# design.net
KiCad netlist of a schematic drawn in Altium Designer
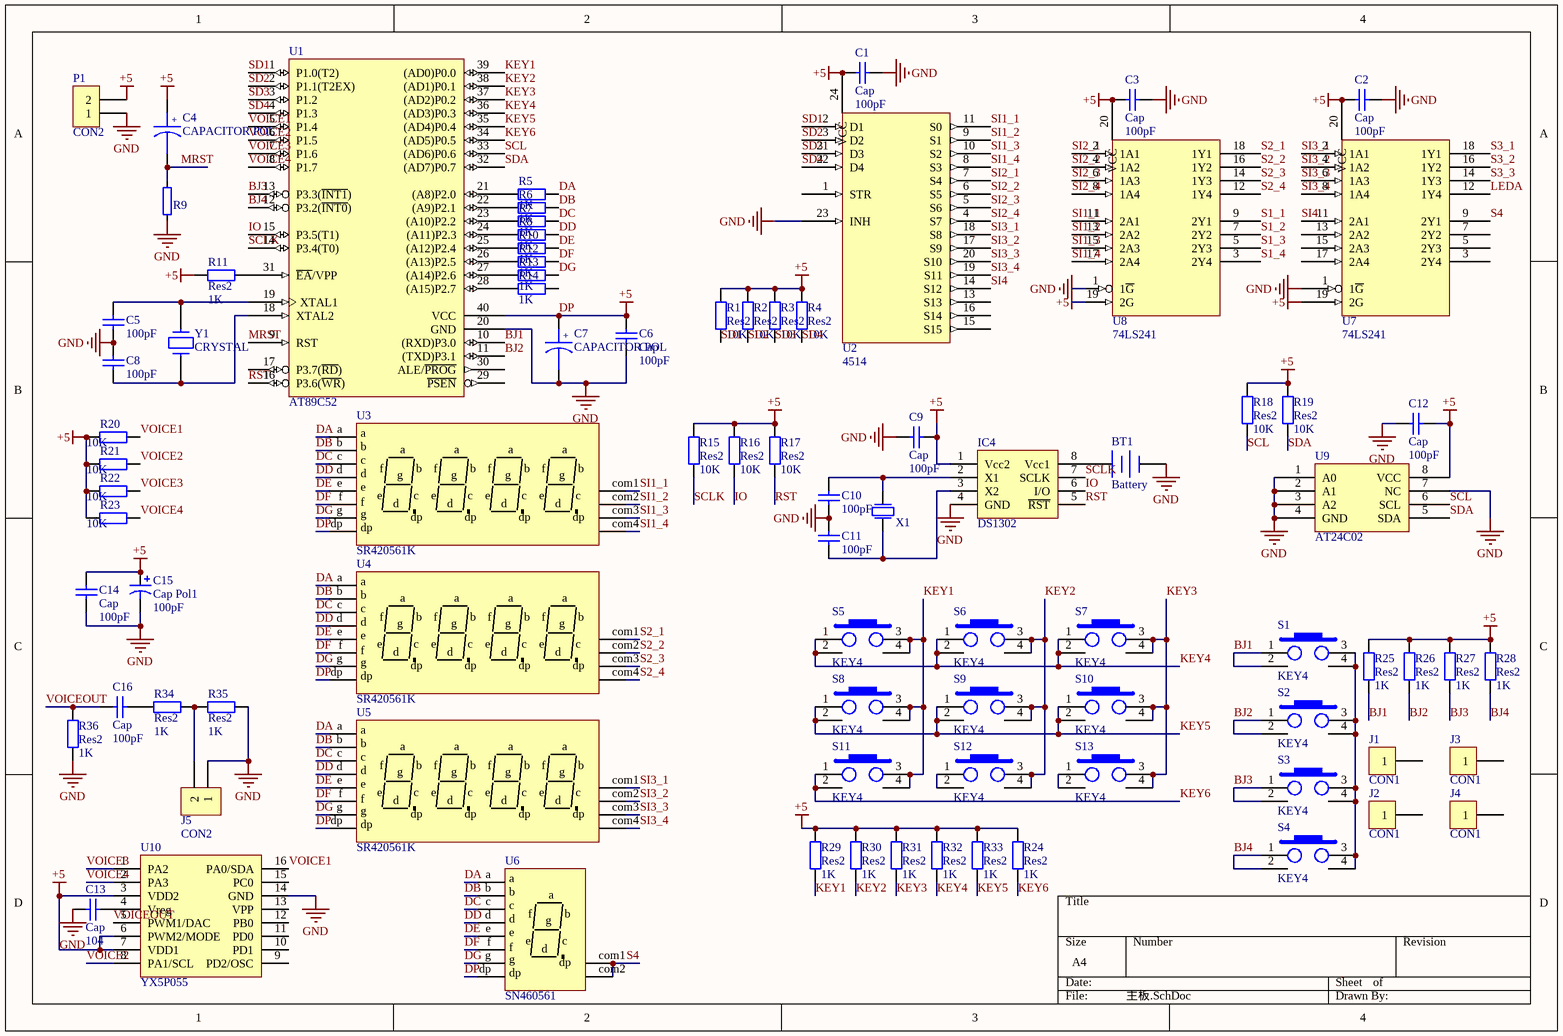
[diagram p0: 主板.SchDoc]

(export (version "E")
  (design (tool "Eeschema 10.0.6"))
  (components
    (comp (ref "BT1")
      (value "Battery")
      (footprint "CR2032-2")
      (description "Multicell Battery")
      (fields (field (name "PUBLISHER") "*"))
      (libsource (lib "mian") (part "Battery"))
    )
    (comp (ref "C1")
      (value "Cap")
      (footprint "RAD-0.3")
      (description "Capacitor")
      (fields (field (name "ALTIUM_VALUE") "100pF") (field (name "PUBLISHER") "Altium Limited"))
      (libsource (lib "Miscellaneous Devices") (part "Cap"))
    )
    (comp (ref "C2")
      (value "Cap")
      (footprint "RAD-0.3")
      (description "Capacitor")
      (fields (field (name "ALTIUM_VALUE") "100pF") (field (name "PUBLISHER") "Altium Limited"))
      (libsource (lib "Miscellaneous Devices") (part "Cap"))
    )
    (comp (ref "C3")
      (value "Cap")
      (footprint "RAD-0.3")
      (description "Capacitor")
      (fields (field (name "ALTIUM_VALUE") "100pF") (field (name "PUBLISHER") "Altium Limited"))
      (libsource (lib "Miscellaneous Devices") (part "Cap"))
    )
    (comp (ref "C4")
      (value "CAPACITOR POL")
      (footprint "22U1")
      (description "Capacitor")
      (libsource (lib "mian") (part "CAPACITOR POL"))
    )
    (comp (ref "C5")
      (value "100pF")
      (footprint "RAD-0.3")
      (description "Capacitor")
      (fields (field (name "Comment") "Cap") (field (name "PUBLISHER") "Altium Limited"))
      (libsource (lib "Miscellaneous Devices") (part "Cap"))
    )
    (comp (ref "C6")
      (value "Cap")
      (footprint "RAD-0.3")
      (description "Capacitor")
      (fields (field (name "ALTIUM_VALUE") "100pF") (field (name "PUBLISHER") "Altium Limited"))
      (libsource (lib "Miscellaneous Devices") (part "Cap"))
    )
    (comp (ref "C7")
      (value "CAPACITOR POL")
      (footprint "22U1")
      (description "Capacitor")
      (libsource (lib "mian") (part "CAPACITOR POL"))
    )
    (comp (ref "C8")
      (value "100pF")
      (footprint "RAD-0.3")
      (description "Capacitor")
      (fields (field (name "Comment") "Cap") (field (name "PUBLISHER") "Altium Limited"))
      (libsource (lib "Miscellaneous Devices") (part "Cap"))
    )
    (comp (ref "C9")
      (value "Cap")
      (footprint "RAD-0.3")
      (description "Capacitor")
      (fields (field (name "ALTIUM_VALUE") "100pF") (field (name "PUBLISHER") "Altium Limited"))
      (libsource (lib "Miscellaneous Devices") (part "Cap"))
    )
    (comp (ref "C10")
      (value "100pF")
      (footprint "RAD-0.3")
      (description "Capacitor")
      (fields (field (name "Comment") "Cap") (field (name "PUBLISHER") "Altium Limited"))
      (libsource (lib "Miscellaneous Devices") (part "Cap"))
    )
    (comp (ref "C11")
      (value "100pF")
      (footprint "RAD-0.3")
      (description "Capacitor")
      (fields (field (name "Comment") "Cap") (field (name "PUBLISHER") "Altium Limited"))
      (libsource (lib "Miscellaneous Devices") (part "Cap"))
    )
    (comp (ref "C12")
      (value "Cap")
      (footprint "RAD-0.3")
      (description "Capacitor")
      (fields (field (name "ALTIUM_VALUE") "100pF") (field (name "PUBLISHER") "Altium Limited"))
      (libsource (lib "Miscellaneous Devices") (part "Cap"))
    )
    (comp (ref "C13")
      (value "Cap")
      (footprint "RAD-0.3")
      (description "Capacitor")
      (fields (field (name "ALTIUM_VALUE") "104") (field (name "PUBLISHER") "Altium Limited"))
      (libsource (lib "Miscellaneous Devices") (part "Cap"))
    )
    (comp (ref "C14")
      (value "Cap")
      (footprint "RAD-0.3")
      (description "Capacitor")
      (fields (field (name "ALTIUM_VALUE") "100pF") (field (name "PUBLISHER") "Altium Limited"))
      (libsource (lib "Miscellaneous Devices") (part "Cap"))
    )
    (comp (ref "C15")
      (value "Cap Pol1")
      (footprint "RB7.6-15")
      (description "Polarized Capacitor (Radial)")
      (fields (field (name "ALTIUM_VALUE") "100pF") (field (name "PUBLISHER") "Altium Limited"))
      (libsource (lib "Miscellaneous Devices") (part "Cap Pol1"))
    )
    (comp (ref "C16")
      (value "Cap")
      (footprint "RAD-0.3")
      (description "Capacitor")
      (fields (field (name "ALTIUM_VALUE") "100pF") (field (name "PUBLISHER") "Altium Limited"))
      (libsource (lib "Miscellaneous Devices") (part "Cap"))
    )
    (comp (ref "IC4") (value "DS1302") (footprint "DIP8") (libsource (lib "mian") (part "DS1302")))
    (comp (ref "J1")
      (value "CON1")
      (footprint "GDK")
      (description "Connector")
      (libsource (lib "mian") (part "CON1"))
    )
    (comp (ref "J2")
      (value "CON1")
      (footprint "GDK")
      (description "Connector")
      (libsource (lib "mian") (part "CON1"))
    )
    (comp (ref "J3")
      (value "CON1")
      (footprint "GDK")
      (description "Connector")
      (libsource (lib "mian") (part "CON1"))
    )
    (comp (ref "J4")
      (value "CON1")
      (footprint "GDK")
      (description "Connector")
      (libsource (lib "mian") (part "CON1"))
    )
    (comp (ref "J5")
      (value "CON2")
      (footprint "VOICE-1")
      (description "Connector")
      (libsource (lib "gf-sch") (part "CON2"))
    )
    (comp (ref "P1")
      (value "CON2")
      (footprint "VOICE-1")
      (description "Connector")
      (libsource (lib "") (part "CON2_1"))
    )
    (comp (ref "R1")
      (value "Res2")
      (footprint "AXIAL-0.4")
      (description "Resistor")
      (fields (field (name "ALTIUM_VALUE") "10K") (field (name "PUBLISHER") "Altium Limited"))
      (libsource (lib "") (part "Res2_2"))
    )
    (comp (ref "R2")
      (value "Res2")
      (footprint "AXIAL-0.4")
      (description "Resistor")
      (fields (field (name "ALTIUM_VALUE") "10K") (field (name "PUBLISHER") "Altium Limited"))
      (libsource (lib "") (part "Res2_2"))
    )
    (comp (ref "R3")
      (value "Res2")
      (footprint "AXIAL-0.4")
      (description "Resistor")
      (fields (field (name "ALTIUM_VALUE") "10K") (field (name "PUBLISHER") "Altium Limited"))
      (libsource (lib "") (part "Res2_2"))
    )
    (comp (ref "R4")
      (value "Res2")
      (footprint "AXIAL-0.4")
      (description "Resistor")
      (fields (field (name "ALTIUM_VALUE") "10K") (field (name "PUBLISHER") "Altium Limited"))
      (libsource (lib "") (part "Res2_2"))
    )
    (comp (ref "R5")
      (value "1K")
      (footprint "AXIAL-0.4")
      (description "Resistor")
      (fields (field (name "Comment") "Res2") (field (name "PUBLISHER") "Altium Limited"))
      (libsource (lib "") (part "Res2_1"))
    )
    (comp (ref "R6")
      (value "1K")
      (footprint "AXIAL-0.4")
      (description "Resistor")
      (fields (field (name "Comment") "Res2") (field (name "PUBLISHER") "Altium Limited"))
      (libsource (lib "") (part "Res2_1"))
    )
    (comp (ref "R7")
      (value "1K")
      (footprint "AXIAL-0.4")
      (description "Resistor")
      (fields (field (name "Comment") "Res2") (field (name "PUBLISHER") "Altium Limited"))
      (libsource (lib "") (part "Res2_1"))
    )
    (comp (ref "R8")
      (value "1K")
      (footprint "AXIAL-0.4")
      (description "Resistor")
      (fields (field (name "Comment") "Res2") (field (name "PUBLISHER") "Altium Limited"))
      (libsource (lib "") (part "Res2_1"))
    )
    (comp (ref "R9")
      (value "R-10K")
      (footprint "0805R")
      (description "resistor")
      (libsource (lib "mian") (part "R-10K"))
    )
    (comp (ref "R10")
      (value "1K")
      (footprint "AXIAL-0.4")
      (description "Resistor")
      (fields (field (name "Comment") "Res2") (field (name "PUBLISHER") "Altium Limited"))
      (libsource (lib "") (part "Res2_1"))
    )
    (comp (ref "R11")
      (value "Res2")
      (footprint "AXIAL-0.4")
      (description "Resistor")
      (fields (field (name "ALTIUM_VALUE") "1K") (field (name "PUBLISHER") "Altium Limited"))
      (libsource (lib "") (part "Res2_1"))
    )
    (comp (ref "R12")
      (value "1K")
      (footprint "AXIAL-0.4")
      (description "Resistor")
      (fields (field (name "Comment") "Res2") (field (name "PUBLISHER") "Altium Limited"))
      (libsource (lib "") (part "Res2_1"))
    )
    (comp (ref "R13")
      (value "1K")
      (footprint "AXIAL-0.4")
      (description "Resistor")
      (fields (field (name "Comment") "Res2") (field (name "PUBLISHER") "Altium Limited"))
      (libsource (lib "") (part "Res2_1"))
    )
    (comp (ref "R14")
      (value "1K")
      (footprint "AXIAL-0.4")
      (description "Resistor")
      (fields (field (name "Comment") "Res2") (field (name "PUBLISHER") "Altium Limited"))
      (libsource (lib "") (part "Res2_1"))
    )
    (comp (ref "R15")
      (value "Res2")
      (footprint "AXIAL-0.4")
      (description "Resistor")
      (fields (field (name "ALTIUM_VALUE") "10K") (field (name "PUBLISHER") "Altium Limited"))
      (libsource (lib "") (part "Res2_2"))
    )
    (comp (ref "R16")
      (value "Res2")
      (footprint "AXIAL-0.4")
      (description "Resistor")
      (fields (field (name "ALTIUM_VALUE") "10K") (field (name "PUBLISHER") "Altium Limited"))
      (libsource (lib "") (part "Res2_2"))
    )
    (comp (ref "R17")
      (value "Res2")
      (footprint "AXIAL-0.4")
      (description "Resistor")
      (fields (field (name "ALTIUM_VALUE") "10K") (field (name "PUBLISHER") "Altium Limited"))
      (libsource (lib "") (part "Res2_2"))
    )
    (comp (ref "R18")
      (value "Res2")
      (footprint "AXIAL-0.4")
      (description "Resistor")
      (fields (field (name "ALTIUM_VALUE") "10K") (field (name "PUBLISHER") "Altium Limited"))
      (libsource (lib "") (part "Res2_2"))
    )
    (comp (ref "R19")
      (value "Res2")
      (footprint "AXIAL-0.4")
      (description "Resistor")
      (fields (field (name "ALTIUM_VALUE") "10K") (field (name "PUBLISHER") "Altium Limited"))
      (libsource (lib "") (part "Res2_2"))
    )
    (comp (ref "R20")
      (value "10K")
      (footprint "AXIAL-0.4")
      (description "Resistor")
      (fields (field (name "Comment") "Res2") (field (name "PUBLISHER") "Altium Limited"))
      (libsource (lib "Miscellaneous Devices") (part "Res2"))
    )
    (comp (ref "R21")
      (value "10K")
      (footprint "AXIAL-0.4")
      (description "Resistor")
      (fields (field (name "Comment") "Res2") (field (name "PUBLISHER") "Altium Limited"))
      (libsource (lib "Miscellaneous Devices") (part "Res2"))
    )
    (comp (ref "R22")
      (value "10K")
      (footprint "AXIAL-0.4")
      (description "Resistor")
      (fields (field (name "Comment") "Res2") (field (name "PUBLISHER") "Altium Limited"))
      (libsource (lib "Miscellaneous Devices") (part "Res2"))
    )
    (comp (ref "R23")
      (value "10K")
      (footprint "AXIAL-0.4")
      (description "Resistor")
      (fields (field (name "Comment") "Res2") (field (name "PUBLISHER") "Altium Limited"))
      (libsource (lib "Miscellaneous Devices") (part "Res2"))
    )
    (comp (ref "R24")
      (value "Res2")
      (footprint "AXIAL-0.4")
      (description "Resistor")
      (fields (field (name "ALTIUM_VALUE") "1K") (field (name "PUBLISHER") "Altium Limited"))
      (libsource (lib "") (part "Res2_2"))
    )
    (comp (ref "R25")
      (value "Res2")
      (footprint "AXIAL-0.4")
      (description "Resistor")
      (fields (field (name "ALTIUM_VALUE") "1K") (field (name "PUBLISHER") "Altium Limited"))
      (libsource (lib "") (part "Res2_2"))
    )
    (comp (ref "R26")
      (value "Res2")
      (footprint "AXIAL-0.4")
      (description "Resistor")
      (fields (field (name "ALTIUM_VALUE") "1K") (field (name "PUBLISHER") "Altium Limited"))
      (libsource (lib "") (part "Res2_2"))
    )
    (comp (ref "R27")
      (value "Res2")
      (footprint "AXIAL-0.4")
      (description "Resistor")
      (fields (field (name "ALTIUM_VALUE") "1K") (field (name "PUBLISHER") "Altium Limited"))
      (libsource (lib "") (part "Res2_2"))
    )
    (comp (ref "R28")
      (value "Res2")
      (footprint "AXIAL-0.4")
      (description "Resistor")
      (fields (field (name "ALTIUM_VALUE") "1K") (field (name "PUBLISHER") "Altium Limited"))
      (libsource (lib "") (part "Res2_2"))
    )
    (comp (ref "R29")
      (value "Res2")
      (footprint "AXIAL-0.4")
      (description "Resistor")
      (fields (field (name "ALTIUM_VALUE") "1K") (field (name "PUBLISHER") "Altium Limited"))
      (libsource (lib "") (part "Res2_2"))
    )
    (comp (ref "R30")
      (value "Res2")
      (footprint "AXIAL-0.4")
      (description "Resistor")
      (fields (field (name "ALTIUM_VALUE") "1K") (field (name "PUBLISHER") "Altium Limited"))
      (libsource (lib "") (part "Res2_2"))
    )
    (comp (ref "R31")
      (value "Res2")
      (footprint "AXIAL-0.4")
      (description "Resistor")
      (fields (field (name "ALTIUM_VALUE") "1K") (field (name "PUBLISHER") "Altium Limited"))
      (libsource (lib "") (part "Res2_2"))
    )
    (comp (ref "R32")
      (value "Res2")
      (footprint "AXIAL-0.4")
      (description "Resistor")
      (fields (field (name "ALTIUM_VALUE") "1K") (field (name "PUBLISHER") "Altium Limited"))
      (libsource (lib "") (part "Res2_2"))
    )
    (comp (ref "R33")
      (value "Res2")
      (footprint "AXIAL-0.4")
      (description "Resistor")
      (fields (field (name "ALTIUM_VALUE") "1K") (field (name "PUBLISHER") "Altium Limited"))
      (libsource (lib "") (part "Res2_2"))
    )
    (comp (ref "R34")
      (value "Res2")
      (footprint "AXIAL-0.4")
      (description "Resistor")
      (fields (field (name "ALTIUM_VALUE") "1K") (field (name "PUBLISHER") "Altium Limited"))
      (libsource (lib "") (part "Res2_1"))
    )
    (comp (ref "R35")
      (value "Res2")
      (footprint "AXIAL-0.4")
      (description "Resistor")
      (fields (field (name "ALTIUM_VALUE") "1K") (field (name "PUBLISHER") "Altium Limited"))
      (libsource (lib "") (part "Res2_1"))
    )
    (comp (ref "R36")
      (value "Res2")
      (footprint "AXIAL-0.4")
      (description "Resistor")
      (fields (field (name "ALTIUM_VALUE") "1K") (field (name "PUBLISHER") "Altium Limited"))
      (libsource (lib "") (part "Res2_2"))
    )
    (comp (ref "S1") (value "KEY4") (footprint "PUSH12") (libsource (lib "mian") (part "KEY4")))
    (comp (ref "S2") (value "KEY4") (footprint "PUSH12") (libsource (lib "mian") (part "KEY4")))
    (comp (ref "S3") (value "KEY4") (footprint "PUSH12") (libsource (lib "mian") (part "KEY4")))
    (comp (ref "S4") (value "KEY4") (footprint "PUSH12") (libsource (lib "mian") (part "KEY4")))
    (comp (ref "S5") (value "KEY4") (footprint "PUSH12") (libsource (lib "mian") (part "KEY4")))
    (comp (ref "S6") (value "KEY4") (footprint "PUSH12") (libsource (lib "mian") (part "KEY4")))
    (comp (ref "S7") (value "KEY4") (footprint "PUSH12") (libsource (lib "mian") (part "KEY4")))
    (comp (ref "S8") (value "KEY4") (footprint "PUSH12") (libsource (lib "mian") (part "KEY4")))
    (comp (ref "S9") (value "KEY4") (footprint "PUSH12") (libsource (lib "mian") (part "KEY4")))
    (comp (ref "S10") (value "KEY4") (footprint "PUSH12") (libsource (lib "mian") (part "KEY4")))
    (comp (ref "S11") (value "KEY4") (footprint "PUSH12") (libsource (lib "mian") (part "KEY4")))
    (comp (ref "S12") (value "KEY4") (footprint "PUSH12") (libsource (lib "mian") (part "KEY4")))
    (comp (ref "S13") (value "KEY4") (footprint "PUSH12") (libsource (lib "mian") (part "KEY4")))
    (comp (ref "U1")
      (value "AT89C52")
      (footprint "DIP40")
      (description "8-Bit Microcontroller with 8K Flash ROM")
      (libsource (lib "mian") (part "AT89C52"))
    )
    (comp (ref "U2") (value "4514") (footprint "SOP4510") (libsource (lib "mian") (part "4514")))
    (comp (ref "U3")
      (value "SR420561K")
      (footprint "5462B")
      (description "CP-SR420561K")
      (libsource (lib "mian") (part "SR420561K"))
    )
    (comp (ref "U4")
      (value "SR420561K")
      (footprint "5462B")
      (description "CP-SR420561K")
      (libsource (lib "mian") (part "SR420561K"))
    )
    (comp (ref "U5")
      (value "SR420561K")
      (footprint "5462B")
      (description "CP-SR420561K")
      (libsource (lib "mian") (part "SR420561K"))
    )
    (comp (ref "U6")
      (value "SN460561")
      (footprint "3121B")
      (description "CP-SN460561K")
      (libsource (lib "mian") (part "SN460561"))
    )
    (comp (ref "U7") (value "74LS241") (footprint "SOP241") (libsource (lib "mian") (part "74LS241")))
    (comp (ref "U8") (value "74LS241") (footprint "SOP241") (libsource (lib "mian") (part "74LS241")))
    (comp (ref "U9")
      (value "AT24C02")
      (footprint "DIP8")
      (description "U?")
      (libsource (lib "mian") (part "AT24C02"))
    )
    (comp (ref "U10") (value "YX5P055") (footprint "DIP16") (libsource (lib "mian2") (part "YX5P055")))
    (comp (ref "X1") (value "XTAL1") (footprint "X2") (libsource (lib "mian") (part "XTAL1")))
    (comp (ref "Y1")
      (value "CRYSTAL")
      (footprint "OSC2PR-1")
      (description "Crystal")
      (libsource (lib "mian") (part "CRYSTAL"))
    )
  )
  (nets
    (net (code "1") (name "+5") (class "Default")
      (node (ref "C1") (pin "2") (pinfunction "2_2") (pintype "passive"))
      (node (ref "C12") (pin "2") (pinfunction "2_2") (pintype "passive"))
      (node (ref "C14") (pin "2") (pinfunction "2_2") (pintype "passive"))
      (node (ref "C15") (pin "1") (pinfunction "1_1") (pintype "passive"))
      (node (ref "C2") (pin "2") (pinfunction "2_2") (pintype "passive"))
      (node (ref "C3") (pin "2") (pinfunction "2_2") (pintype "passive"))
      (node (ref "C4") (pin "1") (pinfunction "1_1") (pintype "passive"))
      (node (ref "C6") (pin "1") (pinfunction "1_1") (pintype "passive"))
      (node (ref "C7") (pin "1") (pinfunction "1_1") (pintype "passive"))
      (node (ref "C9") (pin "2") (pinfunction "2_2") (pintype "passive"))
      (node (ref "IC4") (pin "1") (pinfunction "Vcc2_1") (pintype "passive"))
      (node (ref "P1") (pin "2") (pinfunction "2_2") (pintype "passive"))
      (node (ref "R1") (pin "2") (pinfunction "2_2") (pintype "passive"))
      (node (ref "R11") (pin "1") (pinfunction "1_1") (pintype "passive"))
      (node (ref "R15") (pin "2") (pinfunction "2_2") (pintype "passive"))
      (node (ref "R16") (pin "2") (pinfunction "2_2") (pintype "passive"))
      (node (ref "R17") (pin "2") (pinfunction "2_2") (pintype "passive"))
      (node (ref "R18") (pin "2") (pinfunction "2_2") (pintype "passive"))
      (node (ref "R19") (pin "2") (pinfunction "2_2") (pintype "passive"))
      (node (ref "R2") (pin "2") (pinfunction "2_2") (pintype "passive"))
      (node (ref "R20") (pin "2") (pinfunction "2_2") (pintype "passive"))
      (node (ref "R21") (pin "2") (pinfunction "2_2") (pintype "passive"))
      (node (ref "R22") (pin "2") (pinfunction "2_2") (pintype "passive"))
      (node (ref "R23") (pin "2") (pinfunction "2_2") (pintype "passive"))
      (node (ref "R24") (pin "2") (pinfunction "2_2") (pintype "passive"))
      (node (ref "R25") (pin "2") (pinfunction "2_2") (pintype "passive"))
      (node (ref "R26") (pin "2") (pinfunction "2_2") (pintype "passive"))
      (node (ref "R27") (pin "2") (pinfunction "2_2") (pintype "passive"))
      (node (ref "R28") (pin "2") (pinfunction "2_2") (pintype "passive"))
      (node (ref "R29") (pin "2") (pinfunction "2_2") (pintype "passive"))
      (node (ref "R3") (pin "2") (pinfunction "2_2") (pintype "passive"))
      (node (ref "R30") (pin "2") (pinfunction "2_2") (pintype "passive"))
      (node (ref "R31") (pin "2") (pinfunction "2_2") (pintype "passive"))
      (node (ref "R32") (pin "2") (pinfunction "2_2") (pintype "passive"))
      (node (ref "R33") (pin "2") (pinfunction "2_2") (pintype "passive"))
      (node (ref "R4") (pin "2") (pinfunction "2_2") (pintype "passive"))
      (node (ref "U1") (pin "40") (pinfunction "VCC_40") (pintype "power_in"))
      (node (ref "U10") (pin "3") (pinfunction "VDD2_3") (pintype "passive"))
      (node (ref "U10") (pin "6") (pinfunction "PWM2/MODE_6") (pintype "passive"))
      (node (ref "U10") (pin "7") (pinfunction "VDD1_7") (pintype "passive"))
      (node (ref "U2") (pin "24") (pinfunction "VCC_24") (pintype "power_in"))
      (node (ref "U3") (pin "dp") (pinfunction "dp_dp") (pintype "passive"))
      (node (ref "U4") (pin "dp") (pinfunction "dp_dp") (pintype "passive"))
      (node (ref "U5") (pin "dp") (pinfunction "dp_dp") (pintype "passive"))
      (node (ref "U6") (pin "dp") (pinfunction "dp_dp") (pintype "passive"))
      (node (ref "U7") (pin "19") (pinfunction "2G_19") (pintype "input"))
      (node (ref "U7") (pin "20") (pinfunction "VCC_20") (pintype "power_in"))
      (node (ref "U8") (pin "19") (pinfunction "2G_19") (pintype "input"))
      (node (ref "U8") (pin "20") (pinfunction "VCC_20") (pintype "power_in"))
      (node (ref "U9") (pin "8") (pinfunction "VCC_8") (pintype "passive"))
    )
    (net (code "2") (name "/BJ1") (class "Default")
      (node (ref "R25") (pin "1") (pinfunction "1_1") (pintype "passive"))
      (node (ref "S1") (pin "1") (pintype "passive"))
      (node (ref "S1") (pin "2") (pintype "passive"))
      (node (ref "U1") (pin "10") (pinfunction "(RXD)P3.0_10") (pintype "bidirectional"))
    )
    (net (code "3") (name "/BJ2") (class "Default")
      (node (ref "R26") (pin "1") (pinfunction "1_1") (pintype "passive"))
      (node (ref "S2") (pin "1") (pintype "passive"))
      (node (ref "S2") (pin "2") (pintype "passive"))
      (node (ref "U1") (pin "11") (pinfunction "(TXD)P3.1_11") (pintype "bidirectional"))
    )
    (net (code "4") (name "/BJ3") (class "Default")
      (node (ref "R27") (pin "1") (pinfunction "1_1") (pintype "passive"))
      (node (ref "S3") (pin "1") (pintype "passive"))
      (node (ref "S3") (pin "2") (pintype "passive"))
      (node (ref "U1") (pin "13") (pinfunction "P3.3(~{INT1})_13") (pintype "bidirectional"))
    )
    (net (code "5") (name "/BJ4") (class "Default")
      (node (ref "R28") (pin "1") (pinfunction "1_1") (pintype "passive"))
      (node (ref "S4") (pin "1") (pintype "passive"))
      (node (ref "S4") (pin "2") (pintype "passive"))
      (node (ref "U1") (pin "12") (pinfunction "P3.2(~{INT0})_12") (pintype "bidirectional"))
    )
    (net (code "6") (name "/DA") (class "Default")
      (node (ref "R5") (pin "2") (pinfunction "2_2") (pintype "passive"))
      (node (ref "U3") (pin "a") (pinfunction "a_a") (pintype "passive"))
      (node (ref "U4") (pin "a") (pinfunction "a_a") (pintype "passive"))
      (node (ref "U5") (pin "a") (pinfunction "a_a") (pintype "passive"))
      (node (ref "U6") (pin "a") (pinfunction "a_a") (pintype "passive"))
    )
    (net (code "7") (name "/DB") (class "Default")
      (node (ref "R6") (pin "2") (pinfunction "2_2") (pintype "passive"))
      (node (ref "U3") (pin "b") (pinfunction "b_b") (pintype "passive"))
      (node (ref "U4") (pin "b") (pinfunction "b_b") (pintype "passive"))
      (node (ref "U5") (pin "b") (pinfunction "b_b") (pintype "passive"))
      (node (ref "U6") (pin "b") (pinfunction "b_b") (pintype "passive"))
    )
    (net (code "8") (name "/DC") (class "Default")
      (node (ref "R7") (pin "2") (pinfunction "2_2") (pintype "passive"))
      (node (ref "U3") (pin "c") (pinfunction "c_c") (pintype "passive"))
      (node (ref "U4") (pin "c") (pinfunction "c_c") (pintype "passive"))
      (node (ref "U5") (pin "c") (pinfunction "c_c") (pintype "passive"))
      (node (ref "U6") (pin "c") (pinfunction "c_c") (pintype "passive"))
    )
    (net (code "9") (name "/DD") (class "Default")
      (node (ref "R8") (pin "2") (pinfunction "2_2") (pintype "passive"))
      (node (ref "U3") (pin "d") (pinfunction "d_d") (pintype "passive"))
      (node (ref "U4") (pin "d") (pinfunction "d_d") (pintype "passive"))
      (node (ref "U5") (pin "d") (pinfunction "d_d") (pintype "passive"))
      (node (ref "U6") (pin "d") (pinfunction "d_d") (pintype "passive"))
    )
    (net (code "10") (name "/DE") (class "Default")
      (node (ref "R10") (pin "2") (pinfunction "2_2") (pintype "passive"))
      (node (ref "U3") (pin "e") (pinfunction "e_e") (pintype "passive"))
      (node (ref "U4") (pin "e") (pinfunction "e_e") (pintype "passive"))
      (node (ref "U5") (pin "e") (pinfunction "e_e") (pintype "passive"))
      (node (ref "U6") (pin "e") (pinfunction "e_e") (pintype "passive"))
    )
    (net (code "11") (name "/DF") (class "Default")
      (node (ref "R12") (pin "2") (pinfunction "2_2") (pintype "passive"))
      (node (ref "U3") (pin "f") (pinfunction "f_f") (pintype "passive"))
      (node (ref "U4") (pin "f") (pinfunction "f_f") (pintype "passive"))
      (node (ref "U5") (pin "f") (pinfunction "f_f") (pintype "passive"))
      (node (ref "U6") (pin "f") (pinfunction "f_f") (pintype "passive"))
    )
    (net (code "12") (name "/DG") (class "Default")
      (node (ref "R13") (pin "2") (pinfunction "2_2") (pintype "passive"))
      (node (ref "U3") (pin "g") (pinfunction "g_g") (pintype "passive"))
      (node (ref "U4") (pin "g") (pinfunction "g_g") (pintype "passive"))
      (node (ref "U5") (pin "g") (pinfunction "g_g") (pintype "passive"))
      (node (ref "U6") (pin "g") (pinfunction "g_g") (pintype "passive"))
    )
    (net (code "13") (name "/IO") (class "Default")
      (node (ref "IC4") (pin "6") (pinfunction "I/O_6") (pintype "passive"))
      (node (ref "R16") (pin "1") (pinfunction "1_1") (pintype "passive"))
      (node (ref "U1") (pin "15") (pinfunction "P3.5(T1)_15") (pintype "bidirectional"))
    )
    (net (code "14") (name "/KEY1") (class "Default")
      (node (ref "R29") (pin "1") (pinfunction "1_1") (pintype "passive"))
      (node (ref "S11") (pin "3") (pintype "passive"))
      (node (ref "S11") (pin "4") (pintype "passive"))
      (node (ref "S5") (pin "3") (pintype "passive"))
      (node (ref "S5") (pin "4") (pintype "passive"))
      (node (ref "S8") (pin "3") (pintype "passive"))
      (node (ref "S8") (pin "4") (pintype "passive"))
      (node (ref "U1") (pin "39") (pinfunction "(AD0)P0.0_39") (pintype "bidirectional"))
    )
    (net (code "15") (name "/KEY2") (class "Default")
      (node (ref "R30") (pin "1") (pinfunction "1_1") (pintype "passive"))
      (node (ref "S12") (pin "3") (pintype "passive"))
      (node (ref "S12") (pin "4") (pintype "passive"))
      (node (ref "S6") (pin "3") (pintype "passive"))
      (node (ref "S6") (pin "4") (pintype "passive"))
      (node (ref "S9") (pin "3") (pintype "passive"))
      (node (ref "S9") (pin "4") (pintype "passive"))
      (node (ref "U1") (pin "38") (pinfunction "(AD1)P0.1_38") (pintype "bidirectional"))
    )
    (net (code "16") (name "/KEY3") (class "Default")
      (node (ref "R31") (pin "1") (pinfunction "1_1") (pintype "passive"))
      (node (ref "S10") (pin "3") (pintype "passive"))
      (node (ref "S10") (pin "4") (pintype "passive"))
      (node (ref "S13") (pin "3") (pintype "passive"))
      (node (ref "S13") (pin "4") (pintype "passive"))
      (node (ref "S7") (pin "3") (pintype "passive"))
      (node (ref "S7") (pin "4") (pintype "passive"))
      (node (ref "U1") (pin "37") (pinfunction "(AD2)P0.2_37") (pintype "bidirectional"))
    )
    (net (code "17") (name "/KEY4") (class "Default")
      (node (ref "R32") (pin "1") (pinfunction "1_1") (pintype "passive"))
      (node (ref "S5") (pin "1") (pintype "passive"))
      (node (ref "S5") (pin "2") (pintype "passive"))
      (node (ref "S6") (pin "1") (pintype "passive"))
      (node (ref "S6") (pin "2") (pintype "passive"))
      (node (ref "S7") (pin "1") (pintype "passive"))
      (node (ref "S7") (pin "2") (pintype "passive"))
      (node (ref "U1") (pin "36") (pinfunction "(AD3)P0.3_36") (pintype "bidirectional"))
    )
    (net (code "18") (name "/KEY5") (class "Default")
      (node (ref "R33") (pin "1") (pinfunction "1_1") (pintype "passive"))
      (node (ref "S10") (pin "1") (pintype "passive"))
      (node (ref "S10") (pin "2") (pintype "passive"))
      (node (ref "S8") (pin "1") (pintype "passive"))
      (node (ref "S8") (pin "2") (pintype "passive"))
      (node (ref "S9") (pin "1") (pintype "passive"))
      (node (ref "S9") (pin "2") (pintype "passive"))
      (node (ref "U1") (pin "35") (pinfunction "(AD4)P0.4_35") (pintype "bidirectional"))
    )
    (net (code "19") (name "/KEY6") (class "Default")
      (node (ref "R24") (pin "1") (pinfunction "1_1") (pintype "passive"))
      (node (ref "S11") (pin "1") (pintype "passive"))
      (node (ref "S11") (pin "2") (pintype "passive"))
      (node (ref "U1") (pin "34") (pinfunction "(AD5)P0.5_34") (pintype "bidirectional"))
    )
    (net (code "20") (name "/LEDA") (class "Default")
      (node (ref "U7") (pin "12") (pinfunction "1Y4_12") (pintype "tri_state"))
    )
    (net (code "21") (name "/MRST") (class "Default")
      (node (ref "C4") (pin "2") (pinfunction "2_2") (pintype "passive"))
      (node (ref "R9") (pin "2") (pinfunction "2_2") (pintype "passive"))
      (node (ref "U1") (pin "9") (pinfunction "RST_9") (pintype "input"))
    )
    (net (code "22") (name "/RST") (class "Default")
      (node (ref "IC4") (pin "5") (pinfunction "~{RST}_5") (pintype "passive"))
      (node (ref "R17") (pin "1") (pinfunction "1_1") (pintype "passive"))
      (node (ref "U1") (pin "16") (pinfunction "P3.6(~{WR})_16") (pintype "bidirectional"))
    )
    (net (code "23") (name "/S1_1") (class "Default")
      (node (ref "U8") (pin "9") (pinfunction "2Y1_9") (pintype "tri_state"))
    )
    (net (code "24") (name "/S1_2") (class "Default")
      (node (ref "U8") (pin "7") (pinfunction "2Y2_7") (pintype "tri_state"))
    )
    (net (code "25") (name "/S1_3") (class "Default")
      (node (ref "U8") (pin "5") (pinfunction "2Y3_5") (pintype "tri_state"))
    )
    (net (code "26") (name "/S1_4") (class "Default")
      (node (ref "U8") (pin "3") (pinfunction "2Y4_3") (pintype "tri_state"))
    )
    (net (code "27") (name "/S2_1") (class "Default")
      (node (ref "U4") (pin "com1") (pinfunction "com1_com1") (pintype "passive"))
      (node (ref "U8") (pin "18") (pinfunction "1Y1_18") (pintype "tri_state"))
    )
    (net (code "28") (name "/S2_2") (class "Default")
      (node (ref "U4") (pin "com2") (pinfunction "com2_com2") (pintype "passive"))
      (node (ref "U8") (pin "16") (pinfunction "1Y2_16") (pintype "tri_state"))
    )
    (net (code "29") (name "/S2_3") (class "Default")
      (node (ref "U4") (pin "com3") (pinfunction "com3_com3") (pintype "passive"))
      (node (ref "U8") (pin "14") (pinfunction "1Y3_14") (pintype "tri_state"))
    )
    (net (code "30") (name "/S2_4") (class "Default")
      (node (ref "U4") (pin "com4") (pinfunction "com4_com4") (pintype "passive"))
      (node (ref "U8") (pin "12") (pinfunction "1Y4_12") (pintype "tri_state"))
    )
    (net (code "31") (name "/S3_1") (class "Default")
      (node (ref "U7") (pin "18") (pinfunction "1Y1_18") (pintype "tri_state"))
    )
    (net (code "32") (name "/S3_2") (class "Default")
      (node (ref "U7") (pin "16") (pinfunction "1Y2_16") (pintype "tri_state"))
    )
    (net (code "33") (name "/S3_3") (class "Default")
      (node (ref "U7") (pin "14") (pinfunction "1Y3_14") (pintype "tri_state"))
    )
    (net (code "34") (name "/S4") (class "Default")
      (node (ref "U6") (pin "com1") (pinfunction "com1_com1") (pintype "passive"))
      (node (ref "U6") (pin "com2") (pinfunction "com2_com2") (pintype "passive"))
      (node (ref "U7") (pin "9") (pinfunction "2Y1_9") (pintype "tri_state"))
    )
    (net (code "35") (name "/SCL") (class "Default")
      (node (ref "R18") (pin "1") (pinfunction "1_1") (pintype "passive"))
      (node (ref "U1") (pin "33") (pinfunction "(AD6)P0.6_33") (pintype "bidirectional"))
      (node (ref "U9") (pin "6") (pinfunction "SCL_6") (pintype "passive"))
    )
    (net (code "36") (name "/SCLK") (class "Default")
      (node (ref "IC4") (pin "7") (pinfunction "SCLK_7") (pintype "passive"))
      (node (ref "R15") (pin "1") (pinfunction "1_1") (pintype "passive"))
      (node (ref "U1") (pin "14") (pinfunction "P3.4(T0)_14") (pintype "bidirectional"))
    )
    (net (code "37") (name "/SD1") (class "Default")
      (node (ref "R1") (pin "1") (pinfunction "1_1") (pintype "passive"))
      (node (ref "U1") (pin "1") (pinfunction "P1.0(T2)_1") (pintype "bidirectional"))
      (node (ref "U2") (pin "2") (pinfunction "D1_2") (pintype "input"))
    )
    (net (code "38") (name "/SD2") (class "Default")
      (node (ref "R2") (pin "1") (pinfunction "1_1") (pintype "passive"))
      (node (ref "U1") (pin "2") (pinfunction "P1.1(T2EX)_2") (pintype "bidirectional"))
      (node (ref "U2") (pin "3") (pinfunction "D2_3") (pintype "input"))
    )
    (net (code "39") (name "/SD3") (class "Default")
      (node (ref "R3") (pin "1") (pinfunction "1_1") (pintype "passive"))
      (node (ref "U1") (pin "3") (pinfunction "P1.2_3") (pintype "bidirectional"))
      (node (ref "U2") (pin "21") (pinfunction "D3_21") (pintype "input"))
    )
    (net (code "40") (name "/SD4") (class "Default")
      (node (ref "R4") (pin "1") (pinfunction "1_1") (pintype "passive"))
      (node (ref "U1") (pin "4") (pinfunction "P1.3_4") (pintype "bidirectional"))
      (node (ref "U2") (pin "22") (pinfunction "D4_22") (pintype "input"))
    )
    (net (code "41") (name "/SDA") (class "Default")
      (node (ref "R19") (pin "1") (pinfunction "1_1") (pintype "passive"))
      (node (ref "U1") (pin "32") (pinfunction "(AD7)P0.7_32") (pintype "bidirectional"))
      (node (ref "U9") (pin "5") (pinfunction "SDA_5") (pintype "passive"))
    )
    (net (code "42") (name "/SI1_1") (class "Default")
      (node (ref "U2") (pin "11") (pinfunction "S0_11") (pintype "output"))
      (node (ref "U3") (pin "com1") (pinfunction "com1_com1") (pintype "passive"))
      (node (ref "U8") (pin "11") (pinfunction "2A1_11") (pintype "input"))
    )
    (net (code "43") (name "/SI1_2") (class "Default")
      (node (ref "U2") (pin "9") (pinfunction "S1_9") (pintype "output"))
      (node (ref "U3") (pin "com2") (pinfunction "com2_com2") (pintype "passive"))
      (node (ref "U8") (pin "13") (pinfunction "2A2_13") (pintype "input"))
    )
    (net (code "44") (name "/SI1_3") (class "Default")
      (node (ref "U2") (pin "10") (pinfunction "S2_10") (pintype "output"))
      (node (ref "U3") (pin "com3") (pinfunction "com3_com3") (pintype "passive"))
      (node (ref "U8") (pin "15") (pinfunction "2A3_15") (pintype "input"))
    )
    (net (code "45") (name "/SI1_4") (class "Default")
      (node (ref "U2") (pin "8") (pinfunction "S3_8") (pintype "output"))
      (node (ref "U3") (pin "com4") (pinfunction "com4_com4") (pintype "passive"))
      (node (ref "U8") (pin "17") (pinfunction "2A4_17") (pintype "input"))
    )
    (net (code "46") (name "/SI2_1") (class "Default")
      (node (ref "U2") (pin "7") (pinfunction "S4_7") (pintype "output"))
      (node (ref "U8") (pin "2") (pinfunction "1A1_2") (pintype "input"))
    )
    (net (code "47") (name "/SI2_2") (class "Default")
      (node (ref "U2") (pin "6") (pinfunction "S5_6") (pintype "output"))
      (node (ref "U8") (pin "4") (pinfunction "1A2_4") (pintype "input"))
    )
    (net (code "48") (name "/SI2_3") (class "Default")
      (node (ref "U2") (pin "5") (pinfunction "S6_5") (pintype "output"))
      (node (ref "U8") (pin "6") (pinfunction "1A3_6") (pintype "input"))
    )
    (net (code "49") (name "/SI2_4") (class "Default")
      (node (ref "U2") (pin "4") (pinfunction "S7_4") (pintype "output"))
      (node (ref "U8") (pin "8") (pinfunction "1A4_8") (pintype "input"))
    )
    (net (code "50") (name "/SI3_1") (class "Default")
      (node (ref "U2") (pin "18") (pinfunction "S8_18") (pintype "output"))
      (node (ref "U5") (pin "com1") (pinfunction "com1_com1") (pintype "passive"))
      (node (ref "U7") (pin "2") (pinfunction "1A1_2") (pintype "input"))
    )
    (net (code "51") (name "/SI3_2") (class "Default")
      (node (ref "U2") (pin "17") (pinfunction "S9_17") (pintype "output"))
      (node (ref "U5") (pin "com2") (pinfunction "com2_com2") (pintype "passive"))
      (node (ref "U7") (pin "4") (pinfunction "1A2_4") (pintype "input"))
    )
    (net (code "52") (name "/SI3_3") (class "Default")
      (node (ref "U2") (pin "20") (pinfunction "S10_20") (pintype "output"))
      (node (ref "U5") (pin "com3") (pinfunction "com3_com3") (pintype "passive"))
      (node (ref "U7") (pin "6") (pinfunction "1A3_6") (pintype "input"))
    )
    (net (code "53") (name "/SI3_4") (class "Default")
      (node (ref "U2") (pin "19") (pinfunction "S11_19") (pintype "output"))
      (node (ref "U5") (pin "com4") (pinfunction "com4_com4") (pintype "passive"))
      (node (ref "U7") (pin "8") (pinfunction "1A4_8") (pintype "input"))
    )
    (net (code "54") (name "/SI4") (class "Default")
      (node (ref "U2") (pin "14") (pinfunction "S12_14") (pintype "output"))
      (node (ref "U7") (pin "11") (pinfunction "2A1_11") (pintype "input"))
    )
    (net (code "55") (name "/VOICE1") (class "Default")
      (node (ref "R20") (pin "1") (pinfunction "1_1") (pintype "passive"))
      (node (ref "U1") (pin "5") (pinfunction "P1.4_5") (pintype "bidirectional"))
      (node (ref "U10") (pin "16") (pinfunction "PA0/SDA_16") (pintype "power_in"))
    )
    (net (code "56") (name "/VOICE2") (class "Default")
      (node (ref "R21") (pin "1") (pinfunction "1_1") (pintype "passive"))
      (node (ref "U1") (pin "6") (pinfunction "P1.5_6") (pintype "bidirectional"))
      (node (ref "U10") (pin "8") (pinfunction "PA1/SCL_8") (pintype "passive"))
    )
    (net (code "57") (name "/VOICE3") (class "Default")
      (node (ref "R22") (pin "1") (pinfunction "1_1") (pintype "passive"))
      (node (ref "U1") (pin "7") (pinfunction "P1.6_7") (pintype "bidirectional"))
      (node (ref "U10") (pin "1") (pinfunction "PA2_1") (pintype "passive"))
    )
    (net (code "58") (name "/VOICE4") (class "Default")
      (node (ref "R23") (pin "1") (pinfunction "1_1") (pintype "passive"))
      (node (ref "U1") (pin "8") (pinfunction "P1.7_8") (pintype "bidirectional"))
      (node (ref "U10") (pin "2") (pinfunction "PA3_2") (pintype "passive"))
    )
    (net (code "59") (name "/VOICEOUT") (class "Default")
      (node (ref "C16") (pin "1") (pinfunction "1_1") (pintype "passive"))
      (node (ref "R36") (pin "2") (pinfunction "2_2") (pintype "passive"))
      (node (ref "U10") (pin "5") (pinfunction "PWM1/DAC_5") (pintype "passive"))
    )
    (net (code "60") (name "GND") (class "Default")
      (node (ref "BT1") (pin "2") (pinfunction "-_2") (pintype "passive"))
      (node (ref "C1") (pin "1") (pinfunction "1_1") (pintype "passive"))
      (node (ref "C10") (pin "2") (pinfunction "2_2") (pintype "passive"))
      (node (ref "C11") (pin "1") (pinfunction "1_1") (pintype "passive"))
      (node (ref "C12") (pin "1") (pinfunction "1_1") (pintype "passive"))
      (node (ref "C13") (pin "1") (pinfunction "1_1") (pintype "passive"))
      (node (ref "C14") (pin "1") (pinfunction "1_1") (pintype "passive"))
      (node (ref "C15") (pin "2") (pinfunction "2_2") (pintype "passive"))
      (node (ref "C2") (pin "1") (pinfunction "1_1") (pintype "passive"))
      (node (ref "C3") (pin "1") (pinfunction "1_1") (pintype "passive"))
      (node (ref "C5") (pin "2") (pinfunction "2_2") (pintype "passive"))
      (node (ref "C6") (pin "2") (pinfunction "2_2") (pintype "passive"))
      (node (ref "C7") (pin "2") (pinfunction "2_2") (pintype "passive"))
      (node (ref "C8") (pin "1") (pinfunction "1_1") (pintype "passive"))
      (node (ref "C9") (pin "1") (pinfunction "1_1") (pintype "passive"))
      (node (ref "IC4") (pin "4") (pinfunction "GND_4") (pintype "passive"))
      (node (ref "J5") (pin "1") (pinfunction "1_1") (pintype "passive"))
      (node (ref "P1") (pin "1") (pinfunction "1_1") (pintype "passive"))
      (node (ref "R35") (pin "2") (pinfunction "2_2") (pintype "passive"))
      (node (ref "R36") (pin "1") (pinfunction "1_1") (pintype "passive"))
      (node (ref "R9") (pin "1") (pinfunction "1_1") (pintype "passive"))
      (node (ref "U1") (pin "20") (pinfunction "GND_20") (pintype "power_in"))
      (node (ref "U10") (pin "14") (pinfunction "GND_14") (pintype "passive"))
      (node (ref "U2") (pin "12") (pinfunction "GND_12") (pintype "power_in"))
      (node (ref "U2") (pin "23") (pinfunction "INH_23") (pintype "input"))
      (node (ref "U7") (pin "1") (pinfunction "1~{G}_1") (pintype "input"))
      (node (ref "U7") (pin "10") (pinfunction "GND_10") (pintype "power_in"))
      (node (ref "U8") (pin "1") (pinfunction "1~{G}_1") (pintype "input"))
      (node (ref "U8") (pin "10") (pinfunction "GND_10") (pintype "power_in"))
      (node (ref "U9") (pin "1") (pinfunction "A0_1") (pintype "passive"))
      (node (ref "U9") (pin "2") (pinfunction "A1_2") (pintype "passive"))
      (node (ref "U9") (pin "3") (pinfunction "A2_3") (pintype "passive"))
      (node (ref "U9") (pin "4") (pinfunction "GND_4") (pintype "passive"))
      (node (ref "U9") (pin "7") (pinfunction "NC_7") (pintype "passive"))
    )
    (net (code "61") (name "Net-(BT1-+)") (class "Default")
      (node (ref "BT1") (pin "1") (pinfunction "+_1") (pintype "passive"))
      (node (ref "IC4") (pin "8") (pinfunction "Vcc1_8") (pintype "passive"))
    )
    (net (code "62") (name "Net-(C16-Pad2)") (class "Default")
      (node (ref "C16") (pin "2") (pinfunction "2_2") (pintype "passive"))
      (node (ref "R34") (pin "1") (pinfunction "1_1") (pintype "passive"))
    )
    (net (code "63") (name "Net-(IC4-X1)") (class "Default")
      (node (ref "C10") (pin "1") (pinfunction "1_1") (pintype "passive"))
      (node (ref "IC4") (pin "2") (pinfunction "X1_2") (pintype "passive"))
      (node (ref "X1") (pin "2") (pinfunction "P2_2") (pintype "passive"))
    )
    (net (code "64") (name "Net-(IC4-X2)") (class "Default")
      (node (ref "C11") (pin "2") (pinfunction "2_2") (pintype "passive"))
      (node (ref "IC4") (pin "3") (pinfunction "X2_3") (pintype "passive"))
      (node (ref "X1") (pin "1") (pinfunction "P1_1") (pintype "passive"))
    )
    (net (code "65") (name "Net-(J5-Pad2)") (class "Default")
      (node (ref "J5") (pin "2") (pinfunction "2_2") (pintype "passive"))
      (node (ref "R34") (pin "2") (pinfunction "2_2") (pintype "passive"))
      (node (ref "R35") (pin "1") (pinfunction "1_1") (pintype "passive"))
    )
    (net (code "66") (name "Net-(S1-Pad3)") (class "Default")
      (node (ref "S1") (pin "3") (pintype "passive"))
      (node (ref "S1") (pin "4") (pintype "passive"))
      (node (ref "S2") (pin "3") (pintype "passive"))
      (node (ref "S2") (pin "4") (pintype "passive"))
      (node (ref "S3") (pin "3") (pintype "passive"))
      (node (ref "S3") (pin "4") (pintype "passive"))
      (node (ref "S4") (pin "3") (pintype "passive"))
      (node (ref "S4") (pin "4") (pintype "passive"))
    )
    (net (code "67") (name "Net-(S12-Pad1)") (class "Default")
      (node (ref "S12") (pin "1") (pintype "passive"))
      (node (ref "S12") (pin "2") (pintype "passive"))
    )
    (net (code "68") (name "Net-(S13-Pad1)") (class "Default")
      (node (ref "S13") (pin "1") (pintype "passive"))
      (node (ref "S13") (pin "2") (pintype "passive"))
    )
    (net (code "69") (name "Net-(U1-(A8)P2.0)") (class "Default")
      (node (ref "R5") (pin "1") (pinfunction "1_1") (pintype "passive"))
      (node (ref "U1") (pin "21") (pinfunction "(A8)P2.0_21") (pintype "bidirectional"))
    )
    (net (code "70") (name "Net-(U1-(A9)P2.1)") (class "Default")
      (node (ref "R6") (pin "1") (pinfunction "1_1") (pintype "passive"))
      (node (ref "U1") (pin "22") (pinfunction "(A9)P2.1_22") (pintype "bidirectional"))
    )
    (net (code "71") (name "Net-(U1-(A10)P2.2)") (class "Default")
      (node (ref "R7") (pin "1") (pinfunction "1_1") (pintype "passive"))
      (node (ref "U1") (pin "23") (pinfunction "(A10)P2.2_23") (pintype "bidirectional"))
    )
    (net (code "72") (name "Net-(U1-(A11)P2.3)") (class "Default")
      (node (ref "R8") (pin "1") (pinfunction "1_1") (pintype "passive"))
      (node (ref "U1") (pin "24") (pinfunction "(A11)P2.3_24") (pintype "bidirectional"))
    )
    (net (code "73") (name "Net-(U1-(A12)P2.4)") (class "Default")
      (node (ref "R10") (pin "1") (pinfunction "1_1") (pintype "passive"))
      (node (ref "U1") (pin "25") (pinfunction "(A12)P2.4_25") (pintype "bidirectional"))
    )
    (net (code "74") (name "Net-(U1-(A13)P2.5)") (class "Default")
      (node (ref "R12") (pin "1") (pinfunction "1_1") (pintype "passive"))
      (node (ref "U1") (pin "26") (pinfunction "(A13)P2.5_26") (pintype "bidirectional"))
    )
    (net (code "75") (name "Net-(U1-(A14)P2.6)") (class "Default")
      (node (ref "R13") (pin "1") (pinfunction "1_1") (pintype "passive"))
      (node (ref "U1") (pin "27") (pinfunction "(A14)P2.6_27") (pintype "bidirectional"))
    )
    (net (code "76") (name "Net-(U1-(A15)P2.7)") (class "Default")
      (node (ref "R14") (pin "1") (pinfunction "1_1") (pintype "passive"))
      (node (ref "U1") (pin "28") (pinfunction "(A15)P2.7_28") (pintype "bidirectional"))
    )
    (net (code "77") (name "Net-(U1-XTAL1)") (class "Default")
      (node (ref "C5") (pin "1") (pinfunction "1_1") (pintype "passive"))
      (node (ref "U1") (pin "19") (pinfunction "XTAL1_19") (pintype "input"))
      (node (ref "Y1") (pin "2") (pinfunction "2_2") (pintype "passive"))
    )
    (net (code "78") (name "Net-(U1-XTAL2)") (class "Default")
      (node (ref "C8") (pin "2") (pinfunction "2_2") (pintype "passive"))
      (node (ref "U1") (pin "18") (pinfunction "XTAL2_18") (pintype "input"))
      (node (ref "Y1") (pin "1") (pinfunction "1_1") (pintype "passive"))
    )
    (net (code "79") (name "Net-(U1-~{EA}{slash}VPP)") (class "Default")
      (node (ref "R11") (pin "2") (pinfunction "2_2") (pintype "passive"))
      (node (ref "U1") (pin "31") (pinfunction "~{EA}/VPP_31") (pintype "input"))
    )
    (net (code "80") (name "Net-(U10-Vreg)") (class "Default")
      (node (ref "C13") (pin "2") (pinfunction "2_2") (pintype "passive"))
      (node (ref "U10") (pin "4") (pinfunction "Vreg_4") (pintype "passive"))
    )
    (net (code "81") (name "unconnected-(J1-Pad1)") (class "Default")
      (node (ref "J1") (pin "1") (pinfunction "1_1") (pintype "passive"))
    )
    (net (code "82") (name "unconnected-(J2-Pad1)") (class "Default")
      (node (ref "J2") (pin "1") (pinfunction "1_1") (pintype "passive"))
    )
    (net (code "83") (name "unconnected-(J3-Pad1)") (class "Default")
      (node (ref "J3") (pin "1") (pinfunction "1_1") (pintype "passive"))
    )
    (net (code "84") (name "unconnected-(J4-Pad1)") (class "Default")
      (node (ref "J4") (pin "1") (pinfunction "1_1") (pintype "passive"))
    )
    (net (code "85") (name "unconnected-(R14-Pad2)") (class "Default")
      (node (ref "R14") (pin "2") (pinfunction "2_2") (pintype "passive"))
    )
    (net (code "86") (name "unconnected-(U1-ALE{slash}~{PROG}-Pad30)") (class "Default")
      (node (ref "U1") (pin "30") (pinfunction "ALE/~{PROG}_30") (pintype "output"))
    )
    (net (code "87") (name "unconnected-(U1-P3.7(~{RD})-Pad17)") (class "Default")
      (node (ref "U1") (pin "17") (pinfunction "P3.7(~{RD})_17") (pintype "bidirectional"))
    )
    (net (code "88") (name "unconnected-(U1-~{PSEN}-Pad29)") (class "Default")
      (node (ref "U1") (pin "29") (pinfunction "~{PSEN}_29") (pintype "output"))
    )
    (net (code "89") (name "unconnected-(U2-S13-Pad13)") (class "Default")
      (node (ref "U2") (pin "13") (pinfunction "S13_13") (pintype "output"))
    )
    (net (code "90") (name "unconnected-(U2-S14-Pad16)") (class "Default")
      (node (ref "U2") (pin "16") (pinfunction "S14_16") (pintype "output"))
    )
    (net (code "91") (name "unconnected-(U2-S15-Pad15)") (class "Default")
      (node (ref "U2") (pin "15") (pinfunction "S15_15") (pintype "output"))
    )
    (net (code "92") (name "unconnected-(U2-STR-Pad1)") (class "Default")
      (node (ref "U2") (pin "1") (pinfunction "STR_1") (pintype "input"))
    )
    (net (code "93") (name "unconnected-(U7-2A2-Pad13)") (class "Default")
      (node (ref "U7") (pin "13") (pinfunction "2A2_13") (pintype "input"))
    )
    (net (code "94") (name "unconnected-(U7-2A3-Pad15)") (class "Default")
      (node (ref "U7") (pin "15") (pinfunction "2A3_15") (pintype "input"))
    )
    (net (code "95") (name "unconnected-(U7-2A4-Pad17)") (class "Default")
      (node (ref "U7") (pin "17") (pinfunction "2A4_17") (pintype "input"))
    )
    (net (code "96") (name "unconnected-(U7-2Y2-Pad7)") (class "Default")
      (node (ref "U7") (pin "7") (pinfunction "2Y2_7") (pintype "tri_state"))
    )
    (net (code "97") (name "unconnected-(U7-2Y3-Pad5)") (class "Default")
      (node (ref "U7") (pin "5") (pinfunction "2Y3_5") (pintype "tri_state"))
    )
    (net (code "98") (name "unconnected-(U7-2Y4-Pad3)") (class "Default")
      (node (ref "U7") (pin "3") (pinfunction "2Y4_3") (pintype "tri_state"))
    )
    (net (code "99") (name "unconnected-(U10-PB0-Pad12)") (class "Default")
      (node (ref "U10") (pin "12") (pinfunction "PB0_12") (pintype "passive"))
    )
    (net (code "100") (name "unconnected-(U10-PC0-Pad15)") (class "Default")
      (node (ref "U10") (pin "15") (pinfunction "PC0_15") (pintype "power_in"))
    )
    (net (code "101") (name "unconnected-(U10-PD0-Pad11)") (class "Default")
      (node (ref "U10") (pin "11") (pinfunction "PD0_11") (pintype "passive"))
    )
    (net (code "102") (name "unconnected-(U10-PD1-Pad10)") (class "Default")
      (node (ref "U10") (pin "10") (pinfunction "PD1_10") (pintype "passive"))
    )
    (net (code "103") (name "unconnected-(U10-PD2{slash}OSC-Pad9)") (class "Default")
      (node (ref "U10") (pin "9") (pinfunction "PD2/OSC_9") (pintype "passive"))
    )
    (net (code "104") (name "unconnected-(U10-VPP-Pad13)") (class "Default")
      (node (ref "U10") (pin "13") (pinfunction "VPP_13") (pintype "passive"))
    )
  )
)
